# F28335_USB_and_Nordic.net
KiCad netlist of a schematic drawn in Altium Designer
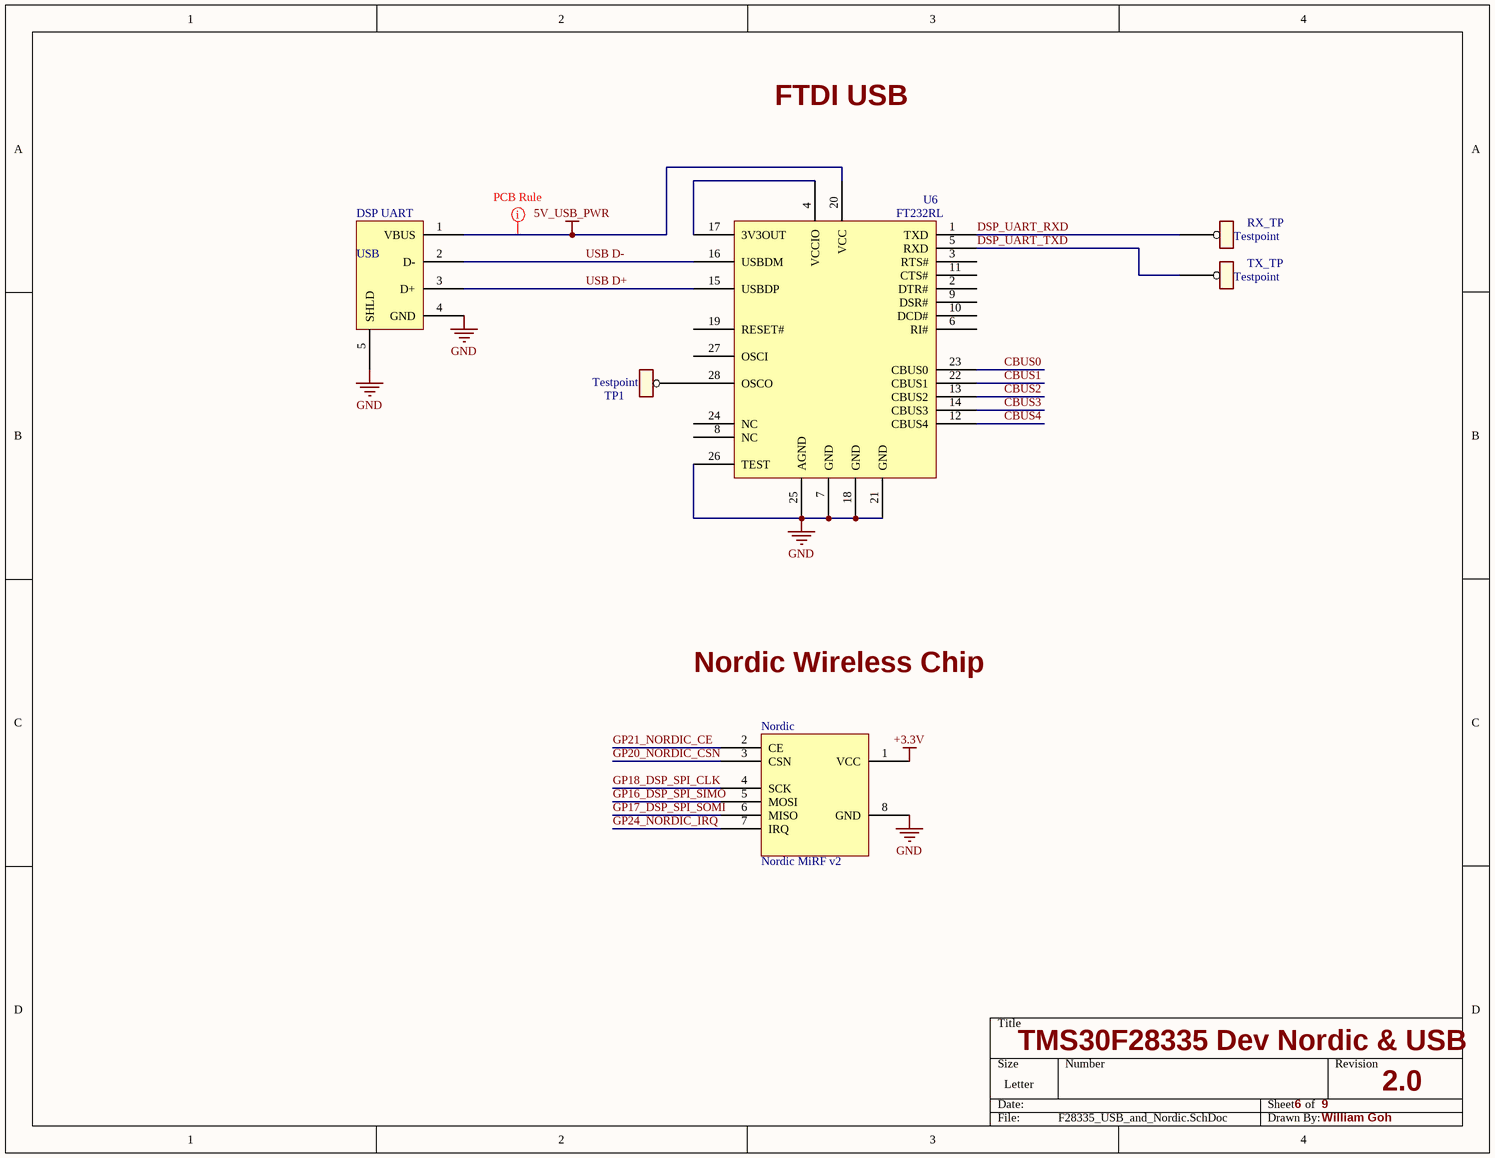
[diagram p0: F28335_USB_and_Nordic.SchDoc]

(export (version "E")
  (design (tool "Eeschema 10.0.6"))
  (components
    (comp (ref "Nordic")
      (value "Nordic MiRF v2")
      (footprint "Nordic MiRF v2")
      (libsource (lib "gohak") (part "Nordic MiRF v2"))
    )
    (comp (ref "RX_TP")
      (value "Testpoint")
      (footprint "TestPoint Trough-Hole")
      (libsource (lib "F28335_DSC_Breakout") (part "Testpoint"))
    )
    (comp (ref "TP1") (value "Testpoint") (libsource (lib "") (part "Testpoint_1")))
    (comp (ref "TX_TP")
      (value "Testpoint")
      (footprint "TestPoint Trough-Hole")
      (libsource (lib "F28335_DSC_Breakout") (part "Testpoint"))
    )
    (comp (ref "U6")
      (value "FT232RL")
      (footprint "SSOP28")
      (description "FTDI FT232RL")
      (libsource (lib "V4_EEL4744") (part "FT232RL"))
    )
    (comp (ref "USB")
      (value "DSP UART")
      (footprint "USB_TypeB_RightAngle")
      (libsource (lib "F28335_DSC_Breakout") (part "USB"))
    )
  )
  (nets
    (net (code "1") (name "+3.3V") (class "Default")
      (node (ref "Nordic") (pin "1") (pinfunction "VCC_1") (pintype "passive"))
    )
    (net (code "2") (name "/CBUS0") (class "Default")
      (node (ref "U6") (pin "23") (pinfunction "CBUS0_23") (pintype "passive"))
    )
    (net (code "3") (name "/CBUS1") (class "Default")
      (node (ref "U6") (pin "22") (pinfunction "CBUS1_22") (pintype "passive"))
    )
    (net (code "4") (name "/CBUS2") (class "Default")
      (node (ref "U6") (pin "13") (pinfunction "CBUS2_13") (pintype "passive"))
    )
    (net (code "5") (name "/CBUS3") (class "Default")
      (node (ref "U6") (pin "14") (pinfunction "CBUS3_14") (pintype "passive"))
    )
    (net (code "6") (name "/CBUS4") (class "Default")
      (node (ref "U6") (pin "12") (pinfunction "CBUS4_12") (pintype "passive"))
    )
    (net (code "7") (name "/DSP_UART_RXD") (class "Default")
      (node (ref "RX_TP") (pin "1") (pinfunction "1_1") (pintype "passive"))
      (node (ref "U6") (pin "1") (pinfunction "TXD_1") (pintype "passive"))
    )
    (net (code "8") (name "/DSP_UART_TXD") (class "Default")
      (node (ref "TX_TP") (pin "1") (pinfunction "1_1") (pintype "passive"))
      (node (ref "U6") (pin "5") (pinfunction "RXD_5") (pintype "passive"))
    )
    (net (code "9") (name "/GP16_DSP_SPI_SIMO") (class "Default")
      (node (ref "Nordic") (pin "5") (pinfunction "MOSI_5") (pintype "passive"))
    )
    (net (code "10") (name "/GP17_DSP_SPI_SOMI") (class "Default")
      (node (ref "Nordic") (pin "6") (pinfunction "MISO_6") (pintype "passive"))
    )
    (net (code "11") (name "/GP18_DSP_SPI_CLK") (class "Default")
      (node (ref "Nordic") (pin "4") (pinfunction "SCK_4") (pintype "passive"))
    )
    (net (code "12") (name "/GP20_NORDIC_CSN") (class "Default")
      (node (ref "Nordic") (pin "3") (pinfunction "CSN_3") (pintype "passive"))
    )
    (net (code "13") (name "/GP21_NORDIC_CE") (class "Default")
      (node (ref "Nordic") (pin "2") (pinfunction "CE_2") (pintype "passive"))
    )
    (net (code "14") (name "/GP24_NORDIC_IRQ") (class "Default")
      (node (ref "Nordic") (pin "7") (pinfunction "IRQ_7") (pintype "passive"))
    )
    (net (code "15") (name "/USB D+") (class "Default")
      (node (ref "U6") (pin "15") (pinfunction "USBDP_15") (pintype "passive"))
      (node (ref "USB") (pin "3") (pinfunction "D+_3") (pintype "passive"))
    )
    (net (code "16") (name "/USB D-") (class "Default")
      (node (ref "U6") (pin "16") (pinfunction "USBDM_16") (pintype "passive"))
      (node (ref "USB") (pin "2") (pinfunction "D-_2") (pintype "passive"))
    )
    (net (code "17") (name "5V_USB_PWR") (class "Default")
      (node (ref "U6") (pin "20") (pinfunction "VCC_20") (pintype "passive"))
      (node (ref "USB") (pin "1") (pinfunction "VBUS_1") (pintype "passive"))
    )
    (net (code "18") (name "GND") (class "Default")
      (node (ref "Nordic") (pin "8") (pinfunction "GND_8") (pintype "passive"))
      (node (ref "U6") (pin "18") (pinfunction "GND_18") (pintype "passive"))
      (node (ref "U6") (pin "21") (pinfunction "GND_21") (pintype "passive"))
      (node (ref "U6") (pin "25") (pinfunction "AGND_25") (pintype "passive"))
      (node (ref "U6") (pin "26") (pinfunction "TEST_26") (pintype "passive"))
      (node (ref "U6") (pin "7") (pinfunction "GND_7") (pintype "passive"))
      (node (ref "USB") (pin "4") (pinfunction "GND_4") (pintype "passive"))
      (node (ref "USB") (pin "5") (pinfunction "SHLD_5") (pintype "passive"))
    )
    (net (code "19") (name "Net-(U6-3V3OUT)") (class "Default")
      (node (ref "U6") (pin "17") (pinfunction "3V3OUT_17") (pintype "passive"))
      (node (ref "U6") (pin "4") (pinfunction "VCCIO_4") (pintype "passive"))
    )
    (net (code "20") (name "Net-(U6-OSCO)") (class "Default")
      (node (ref "TP1") (pin "1") (pinfunction "1_1") (pintype "passive"))
      (node (ref "U6") (pin "28") (pinfunction "OSCO_28") (pintype "passive"))
    )
    (net (code "21") (name "unconnected-(U6-CTS#-Pad11)") (class "Default")
      (node (ref "U6") (pin "11") (pinfunction "CTS#_11") (pintype "passive"))
    )
    (net (code "22") (name "unconnected-(U6-DCD#-Pad10)") (class "Default")
      (node (ref "U6") (pin "10") (pinfunction "DCD#_10") (pintype "passive"))
    )
    (net (code "23") (name "unconnected-(U6-DSR#-Pad9)") (class "Default")
      (node (ref "U6") (pin "9") (pinfunction "DSR#_9") (pintype "passive"))
    )
    (net (code "24") (name "unconnected-(U6-DTR#-Pad2)") (class "Default")
      (node (ref "U6") (pin "2") (pinfunction "DTR#_2") (pintype "passive"))
    )
    (net (code "25") (name "unconnected-(U6-NC-Pad8)") (class "Default")
      (node (ref "U6") (pin "8") (pinfunction "NC_8") (pintype "passive"))
    )
    (net (code "26") (name "unconnected-(U6-NC-Pad24)") (class "Default")
      (node (ref "U6") (pin "24") (pinfunction "NC_24") (pintype "passive"))
    )
    (net (code "27") (name "unconnected-(U6-OSCI-Pad27)") (class "Default")
      (node (ref "U6") (pin "27") (pinfunction "OSCI_27") (pintype "passive"))
    )
    (net (code "28") (name "unconnected-(U6-RESET#-Pad19)") (class "Default")
      (node (ref "U6") (pin "19") (pinfunction "RESET#_19") (pintype "passive"))
    )
    (net (code "29") (name "unconnected-(U6-RI#-Pad6)") (class "Default")
      (node (ref "U6") (pin "6") (pinfunction "RI#_6") (pintype "passive"))
    )
    (net (code "30") (name "unconnected-(U6-RTS#-Pad3)") (class "Default")
      (node (ref "U6") (pin "3") (pinfunction "RTS#_3") (pintype "passive"))
    )
  )
)
